# expansions.net
KiCad netlist of a schematic drawn in Altium Designer
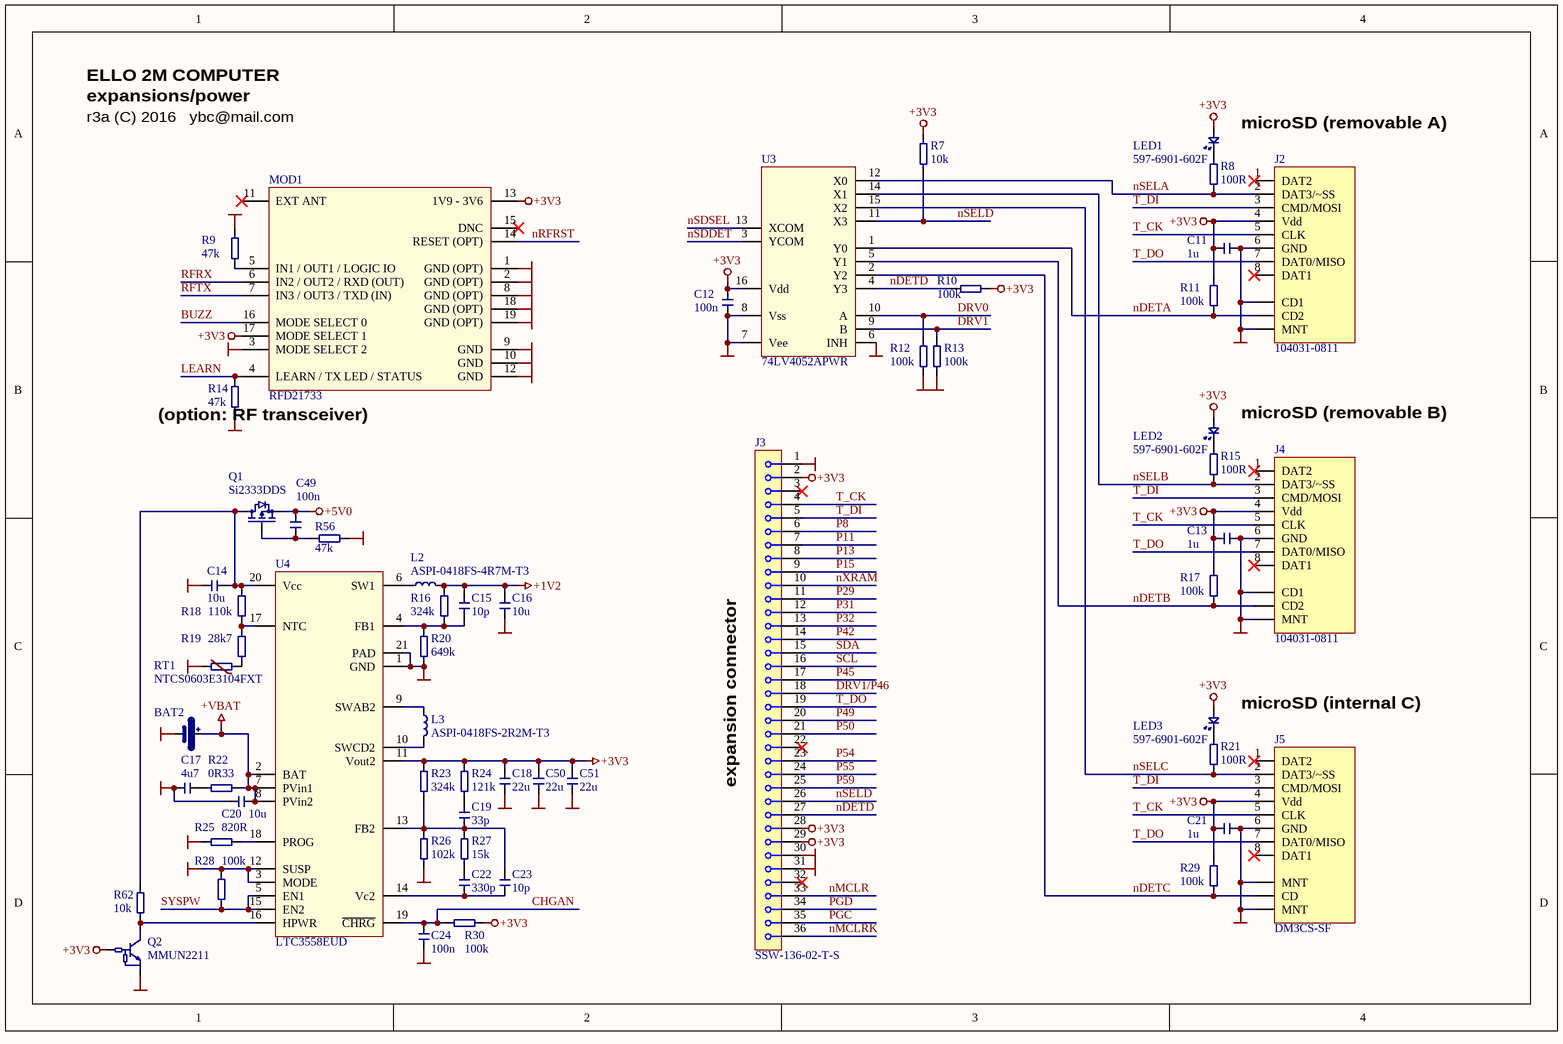
[diagram p0: expansions.SchDoc]

(export (version "E")
  (design (tool "Eeschema 10.0.6"))
  (components
    (comp (ref "BAT2") (value "Battery") (footprint "Bat_Holder1") (libsource (lib "Misc") (part "Battery")))
    (comp (ref "C11")
      (value "1u")
      (footprint "_0603")
      (description "Capacitor")
      (libsource (lib "Discretes") (part "Capacitor"))
    )
    (comp (ref "C12")
      (value "100n")
      (footprint "_0603")
      (description "Capacitor")
      (libsource (lib "Discretes") (part "Capacitor"))
    )
    (comp (ref "C13")
      (value "1u")
      (footprint "_0603")
      (description "Capacitor")
      (libsource (lib "Discretes") (part "Capacitor"))
    )
    (comp (ref "C14")
      (value "10u")
      (footprint "_1206")
      (description "Capacitor")
      (libsource (lib "Discretes") (part "Capacitor"))
    )
    (comp (ref "C15")
      (value "10p")
      (footprint "_0603")
      (description "Capacitor")
      (libsource (lib "Discretes") (part "Capacitor"))
    )
    (comp (ref "C16")
      (value "10u")
      (footprint "_1206")
      (description "Capacitor")
      (libsource (lib "Discretes") (part "Capacitor"))
    )
    (comp (ref "C17")
      (value "4u7")
      (footprint "_1206")
      (description "Capacitor")
      (libsource (lib "Discretes") (part "Capacitor"))
    )
    (comp (ref "C18")
      (value "22u")
      (footprint "_1206")
      (description "Capacitor")
      (libsource (lib "Discretes") (part "Capacitor"))
    )
    (comp (ref "C19")
      (value "33p")
      (footprint "_0603")
      (description "Capacitor")
      (libsource (lib "Discretes") (part "Capacitor"))
    )
    (comp (ref "C20")
      (value "10u")
      (footprint "_1206")
      (description "Capacitor")
      (libsource (lib "Discretes") (part "Capacitor"))
    )
    (comp (ref "C21")
      (value "1u")
      (footprint "_0603")
      (description "Capacitor")
      (libsource (lib "Discretes") (part "Capacitor"))
    )
    (comp (ref "C22")
      (value "330p")
      (footprint "_0603")
      (description "Capacitor")
      (libsource (lib "Discretes") (part "Capacitor"))
    )
    (comp (ref "C23")
      (value "10p")
      (footprint "_0603")
      (description "Capacitor")
      (libsource (lib "Discretes") (part "Capacitor"))
    )
    (comp (ref "C24")
      (value "100n")
      (footprint "_0603")
      (description "Capacitor")
      (libsource (lib "Discretes") (part "Capacitor"))
    )
    (comp (ref "C49")
      (value "100n")
      (footprint "_0603")
      (description "Capacitor")
      (libsource (lib "Discretes") (part "Capacitor"))
    )
    (comp (ref "C50")
      (value "22u")
      (footprint "_1206")
      (description "Capacitor")
      (libsource (lib "Discretes") (part "Capacitor"))
    )
    (comp (ref "C51")
      (value "22u")
      (footprint "_1206")
      (description "Capacitor")
      (libsource (lib "Discretes") (part "Capacitor"))
    )
    (comp (ref "J2")
      (value "104031-0811")
      (footprint "MOLEX_104031")
      (description "microSD card connector")
      (libsource (lib "Connectors") (part "microSD (w/ card detect)"))
    )
    (comp (ref "J3")
      (value "SSW-136-02-T-S")
      (footprint "SSW-136-02-T-S")
      (description "Single row, 36-way connector")
      (libsource (lib "Connectors") (part "Connector 1x36"))
    )
    (comp (ref "J4")
      (value "104031-0811")
      (footprint "MOLEX_104031")
      (description "microSD card connector")
      (libsource (lib "Connectors") (part "microSD (w/ card detect)"))
    )
    (comp (ref "J5")
      (value "DM3CS-SF")
      (footprint "DM3CS-SF")
      (description "microSD card connector")
      (libsource (lib "") (part "microSD (w/ card detect)_1"))
    )
    (comp (ref "L2")
      (value "ASPI-0418FS-4R7M-T3")
      (footprint "IND_4x4")
      (description "Inductor")
      (libsource (lib "") (part "Inductor_1"))
    )
    (comp (ref "L3")
      (value "ASPI-0418FS-2R2M-T3")
      (footprint "IND_4x4")
      (description "Inductor")
      (libsource (lib "Discretes") (part "Inductor"))
    )
    (comp (ref "LED1")
      (value "597-6901-602F")
      (footprint "LED1206 BOTTOM ENTRY")
      (description "Light Emitting Diode")
      (libsource (lib "Discretes") (part "LED"))
    )
    (comp (ref "LED2")
      (value "597-6901-602F")
      (footprint "LED1206 BOTTOM ENTRY")
      (description "Light Emitting Diode")
      (libsource (lib "Discretes") (part "LED"))
    )
    (comp (ref "LED3")
      (value "597-6901-602F")
      (footprint "LED1206 BOTTOM ENTRY")
      (description "Light Emitting Diode")
      (libsource (lib "Discretes") (part "LED"))
    )
    (comp (ref "MOD1")
      (value "RFD21733")
      (footprint "RFDP8")
      (description "Complete 2.4GHz RF transceiver module with built-in RFDP8 application protocol")
      (fields (field (name "MANUFACTURER") "RF Digital"))
      (libsource (lib "Modules") (part "RFDP8"))
    )
    (comp (ref "Q1")
      (value "Si2333DDS")
      (footprint "SOT23-3")
      (description "P-channel FET transistor")
      (libsource (lib "Discretes") (part "P-FET"))
    )
    (comp (ref "Q2")
      (value "MMUN2211")
      (footprint "SOT23-3")
      (description "NPN biased bipolar transistor")
      (libsource (lib "Discretes") (part "NPN BIASED"))
    )
    (comp (ref "R7")
      (value "10k")
      (footprint "_0603")
      (description "Resistor")
      (libsource (lib "") (part "Resistor_1"))
    )
    (comp (ref "R8")
      (value "100R")
      (footprint "_0603")
      (description "Resistor")
      (libsource (lib "") (part "Resistor_2"))
    )
    (comp (ref "R9")
      (value "47k")
      (footprint "_0603")
      (description "Resistor")
      (libsource (lib "") (part "Resistor_1"))
    )
    (comp (ref "R10")
      (value "100k")
      (footprint "_0603")
      (description "Resistor")
      (libsource (lib "") (part "Resistor_3"))
    )
    (comp (ref "R11")
      (value "100k")
      (footprint "_0603")
      (description "Resistor")
      (libsource (lib "") (part "Resistor_2"))
    )
    (comp (ref "R12")
      (value "100k")
      (footprint "_0603")
      (description "Resistor")
      (libsource (lib "") (part "Resistor_1"))
    )
    (comp (ref "R13")
      (value "100k")
      (footprint "_0603")
      (description "Resistor")
      (libsource (lib "") (part "Resistor_1"))
    )
    (comp (ref "R14")
      (value "47k")
      (footprint "_0603")
      (description "Resistor")
      (libsource (lib "") (part "Resistor_1"))
    )
    (comp (ref "R15")
      (value "100R")
      (footprint "_0603")
      (description "Resistor")
      (libsource (lib "") (part "Resistor_2"))
    )
    (comp (ref "R16")
      (value "324k")
      (footprint "_0603")
      (description "Resistor")
      (libsource (lib "Discretes") (part "Resistor"))
    )
    (comp (ref "R17")
      (value "100k")
      (footprint "_0603")
      (description "Resistor")
      (libsource (lib "") (part "Resistor_2"))
    )
    (comp (ref "R18")
      (value "110k")
      (footprint "_0603")
      (description "Resistor")
      (libsource (lib "Discretes") (part "Resistor"))
    )
    (comp (ref "R19")
      (value "28k7")
      (footprint "_0603")
      (description "Resistor")
      (libsource (lib "Discretes") (part "Resistor"))
    )
    (comp (ref "R20")
      (value "649k")
      (footprint "_0603")
      (description "Resistor")
      (libsource (lib "Discretes") (part "Resistor"))
    )
    (comp (ref "R21")
      (value "100R")
      (footprint "_0603")
      (description "Resistor")
      (libsource (lib "") (part "Resistor_2"))
    )
    (comp (ref "R22")
      (value "0R33")
      (footprint "_1206")
      (description "Resistor")
      (libsource (lib "") (part "Resistor_1"))
    )
    (comp (ref "R23")
      (value "324k")
      (footprint "_0603")
      (description "Resistor")
      (libsource (lib "Discretes") (part "Resistor"))
    )
    (comp (ref "R24")
      (value "121k")
      (footprint "_0603")
      (description "Resistor")
      (libsource (lib "Discretes") (part "Resistor"))
    )
    (comp (ref "R25")
      (value "820R")
      (footprint "_0603")
      (description "Resistor")
      (libsource (lib "") (part "Resistor_1"))
    )
    (comp (ref "R26")
      (value "102k")
      (footprint "_0603")
      (description "Resistor")
      (libsource (lib "Discretes") (part "Resistor"))
    )
    (comp (ref "R27")
      (value "15k")
      (footprint "_0603")
      (description "Resistor")
      (libsource (lib "Discretes") (part "Resistor"))
    )
    (comp (ref "R28")
      (value "100k")
      (footprint "_0603")
      (description "Resistor")
      (libsource (lib "Discretes") (part "Resistor"))
    )
    (comp (ref "R29")
      (value "100k")
      (footprint "_0603")
      (description "Resistor")
      (libsource (lib "") (part "Resistor_2"))
    )
    (comp (ref "R30")
      (value "100k")
      (footprint "_0603")
      (description "Resistor")
      (libsource (lib "") (part "Resistor_1"))
    )
    (comp (ref "R56")
      (value "47k")
      (footprint "_0603")
      (description "Resistor")
      (libsource (lib "") (part "Resistor_1"))
    )
    (comp (ref "R62")
      (value "10k")
      (footprint "_0603")
      (description "Resistor")
      (libsource (lib "Discretes") (part "Resistor"))
    )
    (comp (ref "RT1")
      (value "NTCS0603E3104FXT")
      (footprint "_0603")
      (description "Thermistor")
      (libsource (lib "Discretes") (part "Thermistor"))
    )
    (comp (ref "U3")
      (value "74LV4052APWR")
      (footprint "SOP65P640X120-16N")
      (description "Quad CMOS Analog Multiplexers/Demultiplexers with Logic Level Conversion")
      (libsource (lib "IC Drivers and Switches") (part "4052"))
    )
    (comp (ref "U4")
      (value "LTC3558EUD")
      (footprint "QFN40P300X300X70_HS-21N")
      (description "Linear USB Battery Charger with Buck and Buck-Boost Regulators")
      (fields (field (name "MANUFACTURER") "Linear"))
      (libsource (lib "IC Power Supply") (part "LTC3558"))
    )
  )
  (nets
    (net (code "1") (name "+1V2") (class "Default")
      (node (ref "C15") (pin "2") (pintype "passive"))
      (node (ref "C16") (pin "2") (pintype "passive"))
      (node (ref "L2") (pin "1") (pintype "passive"))
      (node (ref "R16") (pin "1") (pintype "passive"))
    )
    (net (code "2") (name "+3V3") (class "Default")
      (node (ref "C11") (pin "1") (pintype "passive"))
      (node (ref "C12") (pin "2") (pintype "passive"))
      (node (ref "C13") (pin "1") (pintype "passive"))
      (node (ref "C18") (pin "2") (pintype "passive"))
      (node (ref "C21") (pin "1") (pintype "passive"))
      (node (ref "C50") (pin "2") (pintype "passive"))
      (node (ref "C51") (pin "2") (pintype "passive"))
      (node (ref "J2") (pin "4") (pinfunction "Vdd_4") (pintype "passive"))
      (node (ref "J3") (pin "2") (pinfunction "2_2") (pintype "passive"))
      (node (ref "J3") (pin "28") (pinfunction "28_28") (pintype "passive"))
      (node (ref "J3") (pin "29") (pinfunction "29_29") (pintype "passive"))
      (node (ref "J4") (pin "4") (pinfunction "Vdd_4") (pintype "passive"))
      (node (ref "J5") (pin "4") (pinfunction "Vdd_4") (pintype "passive"))
      (node (ref "LED1") (pin "2") (pintype "passive"))
      (node (ref "LED2") (pin "2") (pintype "passive"))
      (node (ref "LED3") (pin "2") (pintype "passive"))
      (node (ref "MOD1") (pin "13") (pinfunction "1V9_-_3V6_13") (pintype "power_in"))
      (node (ref "MOD1") (pin "17") (pinfunction "MODE_SELECT_1_17") (pintype "passive"))
      (node (ref "Q2") (pin "1") (pinfunction "B_1") (pintype "passive"))
      (node (ref "R10") (pin "2") (pintype "passive"))
      (node (ref "R11") (pin "1") (pintype "passive"))
      (node (ref "R17") (pin "1") (pintype "passive"))
      (node (ref "R23") (pin "1") (pintype "passive"))
      (node (ref "R24") (pin "1") (pintype "passive"))
      (node (ref "R29") (pin "1") (pintype "passive"))
      (node (ref "R30") (pin "2") (pintype "passive"))
      (node (ref "R7") (pin "2") (pintype "passive"))
      (node (ref "U3") (pin "16") (pinfunction "Vdd_16") (pintype "passive"))
      (node (ref "U4") (pin "11") (pinfunction "Vout2_11") (pintype "passive"))
    )
    (net (code "3") (name "+5V0") (class "Default")
      (node (ref "C49") (pin "2") (pintype "passive"))
      (node (ref "Q1") (pin "2") (pinfunction "S_2") (pintype "passive"))
    )
    (net (code "4") (name "+VBAT") (class "Default")
      (node (ref "BAT2") (pin "1") (pintype "passive"))
      (node (ref "C20") (pin "2") (pintype "passive"))
      (node (ref "R22") (pin "2") (pintype "passive"))
      (node (ref "U4") (pin "2") (pinfunction "BAT_2") (pintype "passive"))
      (node (ref "U4") (pin "7") (pinfunction "PVin1_7") (pintype "passive"))
      (node (ref "U4") (pin "8") (pinfunction "PVin2_8") (pintype "passive"))
    )
    (net (code "5") (name "/BUZZ") (class "Default")
      (node (ref "MOD1") (pin "16") (pinfunction "MODE_SELECT_0_16") (pintype "passive"))
    )
    (net (code "6") (name "/CHGAN") (class "Default")
      (node (ref "C24") (pin "1") (pintype "passive"))
      (node (ref "R30") (pin "1") (pintype "passive"))
      (node (ref "U4") (pin "19") (pinfunction "~{CHRG}_19") (pintype "passive"))
    )
    (net (code "7") (name "/DRV0") (class "Default")
      (node (ref "R12") (pin "2") (pintype "passive"))
      (node (ref "U3") (pin "10") (pinfunction "A_10") (pintype "passive"))
    )
    (net (code "8") (name "/DRV1") (class "Default")
      (node (ref "R13") (pin "2") (pintype "passive"))
      (node (ref "U3") (pin "9") (pinfunction "B_9") (pintype "passive"))
    )
    (net (code "9") (name "/DRV1{slash}P46") (class "Default")
      (node (ref "J3") (pin "18") (pinfunction "18_18") (pintype "passive"))
    )
    (net (code "10") (name "/LEARN") (class "Default")
      (node (ref "MOD1") (pin "4") (pinfunction "LEARN_/_TX_LED_/_STATUS_4") (pintype "passive"))
      (node (ref "R14") (pin "2") (pintype "passive"))
    )
    (net (code "11") (name "/P8") (class "Default")
      (node (ref "J3") (pin "6") (pinfunction "6_6") (pintype "passive"))
    )
    (net (code "12") (name "/P11") (class "Default")
      (node (ref "J3") (pin "7") (pinfunction "7_7") (pintype "passive"))
    )
    (net (code "13") (name "/P13") (class "Default")
      (node (ref "J3") (pin "8") (pinfunction "8_8") (pintype "passive"))
    )
    (net (code "14") (name "/P15") (class "Default")
      (node (ref "J3") (pin "9") (pinfunction "9_9") (pintype "passive"))
    )
    (net (code "15") (name "/P29") (class "Default")
      (node (ref "J3") (pin "11") (pinfunction "11_11") (pintype "passive"))
    )
    (net (code "16") (name "/P31") (class "Default")
      (node (ref "J3") (pin "12") (pinfunction "12_12") (pintype "passive"))
    )
    (net (code "17") (name "/P32") (class "Default")
      (node (ref "J3") (pin "13") (pinfunction "13_13") (pintype "passive"))
    )
    (net (code "18") (name "/P42") (class "Default")
      (node (ref "J3") (pin "14") (pinfunction "14_14") (pintype "passive"))
    )
    (net (code "19") (name "/P45") (class "Default")
      (node (ref "J3") (pin "17") (pinfunction "17_17") (pintype "passive"))
    )
    (net (code "20") (name "/P49") (class "Default")
      (node (ref "J3") (pin "20") (pinfunction "20_20") (pintype "passive"))
    )
    (net (code "21") (name "/P50") (class "Default")
      (node (ref "J3") (pin "21") (pinfunction "21_21") (pintype "passive"))
    )
    (net (code "22") (name "/P54") (class "Default")
      (node (ref "J3") (pin "23") (pinfunction "23_23") (pintype "passive"))
    )
    (net (code "23") (name "/P55") (class "Default")
      (node (ref "J3") (pin "24") (pinfunction "24_24") (pintype "passive"))
    )
    (net (code "24") (name "/P59") (class "Default")
      (node (ref "J3") (pin "25") (pinfunction "25_25") (pintype "passive"))
    )
    (net (code "25") (name "/PGC") (class "Default")
      (node (ref "J3") (pin "35") (pinfunction "35_35") (pintype "passive"))
    )
    (net (code "26") (name "/PGD") (class "Default")
      (node (ref "J3") (pin "34") (pinfunction "34_34") (pintype "passive"))
    )
    (net (code "27") (name "/RFRX") (class "Default")
      (node (ref "MOD1") (pin "6") (pinfunction "IN2_/_OUT2_/_RXD_(OUT)_6") (pintype "passive"))
    )
    (net (code "28") (name "/RFTX") (class "Default")
      (node (ref "MOD1") (pin "7") (pinfunction "IN3_/_OUT3_/_TXD_(IN)_7") (pintype "passive"))
    )
    (net (code "29") (name "/SCL") (class "Default")
      (node (ref "J3") (pin "16") (pinfunction "16_16") (pintype "passive"))
    )
    (net (code "30") (name "/SDA") (class "Default")
      (node (ref "J3") (pin "15") (pinfunction "15_15") (pintype "passive"))
    )
    (net (code "31") (name "/SYSPW") (class "Default")
      (node (ref "R28") (pin "2") (pintype "passive"))
      (node (ref "U4") (pin "15") (pinfunction "EN2_15") (pintype "passive"))
      (node (ref "U4") (pin "5") (pinfunction "EN1_5") (pintype "passive"))
    )
    (net (code "32") (name "/T_CK") (class "Default")
      (node (ref "J2") (pin "5") (pinfunction "CLK_5") (pintype "passive"))
      (node (ref "J3") (pin "4") (pinfunction "4_4") (pintype "passive"))
      (node (ref "J4") (pin "5") (pinfunction "CLK_5") (pintype "passive"))
      (node (ref "J5") (pin "5") (pinfunction "CLK_5") (pintype "passive"))
    )
    (net (code "33") (name "/T_DI") (class "Default")
      (node (ref "J2") (pin "3") (pinfunction "CMD/MOSI_3") (pintype "passive"))
      (node (ref "J3") (pin "5") (pinfunction "5_5") (pintype "passive"))
      (node (ref "J4") (pin "3") (pinfunction "CMD/MOSI_3") (pintype "passive"))
      (node (ref "J5") (pin "3") (pinfunction "CMD/MOSI_3") (pintype "passive"))
    )
    (net (code "34") (name "/T_DO") (class "Default")
      (node (ref "J2") (pin "7") (pinfunction "DAT0/MISO_7") (pintype "passive"))
      (node (ref "J3") (pin "19") (pinfunction "19_19") (pintype "passive"))
      (node (ref "J4") (pin "7") (pinfunction "DAT0/MISO_7") (pintype "passive"))
      (node (ref "J5") (pin "7") (pinfunction "DAT0/MISO_7") (pintype "passive"))
    )
    (net (code "35") (name "/nDETA") (class "Default")
      (node (ref "J2") (pin "CD2") (pinfunction "CD2_CD2") (pintype "passive"))
      (node (ref "R11") (pin "2") (pintype "passive"))
      (node (ref "U3") (pin "1") (pinfunction "Y0_1") (pintype "passive"))
    )
    (net (code "36") (name "/nDETB") (class "Default")
      (node (ref "J4") (pin "CD2") (pinfunction "CD2_CD2") (pintype "passive"))
      (node (ref "R17") (pin "2") (pintype "passive"))
      (node (ref "U3") (pin "5") (pinfunction "Y1_5") (pintype "passive"))
    )
    (net (code "37") (name "/nDETC") (class "Default")
      (node (ref "J5") (pin "CD") (pinfunction "CD_CD") (pintype "passive"))
      (node (ref "R29") (pin "2") (pintype "passive"))
      (node (ref "U3") (pin "2") (pinfunction "Y2_2") (pintype "passive"))
    )
    (net (code "38") (name "/nDETD") (class "Default")
      (node (ref "J3") (pin "27") (pinfunction "27_27") (pintype "passive"))
      (node (ref "R10") (pin "1") (pintype "passive"))
      (node (ref "U3") (pin "4") (pinfunction "Y3_4") (pintype "passive"))
    )
    (net (code "39") (name "/nMCLR") (class "Default")
      (node (ref "J3") (pin "33") (pinfunction "33_33") (pintype "passive"))
    )
    (net (code "40") (name "/nMCLRK") (class "Default")
      (node (ref "J3") (pin "36") (pinfunction "36_36") (pintype "passive"))
    )
    (net (code "41") (name "/nRFRST") (class "Default")
      (node (ref "MOD1") (pin "14") (pinfunction "RESET_(OPT)_14") (pintype "passive"))
    )
    (net (code "42") (name "/nSDDET") (class "Default")
      (node (ref "U3") (pin "3") (pinfunction "YCOM_3") (pintype "passive"))
    )
    (net (code "43") (name "/nSDSEL") (class "Default")
      (node (ref "U3") (pin "13") (pinfunction "XCOM_13") (pintype "passive"))
    )
    (net (code "44") (name "/nSELA") (class "Default")
      (node (ref "J2") (pin "2") (pinfunction "DAT3/~SS_2") (pintype "passive"))
      (node (ref "R8") (pin "2") (pintype "passive"))
      (node (ref "U3") (pin "12") (pinfunction "X0_12") (pintype "passive"))
    )
    (net (code "45") (name "/nSELB") (class "Default")
      (node (ref "J4") (pin "2") (pinfunction "DAT3/~SS_2") (pintype "passive"))
      (node (ref "R15") (pin "2") (pintype "passive"))
      (node (ref "U3") (pin "14") (pinfunction "X1_14") (pintype "passive"))
    )
    (net (code "46") (name "/nSELC") (class "Default")
      (node (ref "J5") (pin "2") (pinfunction "DAT3/~SS_2") (pintype "passive"))
      (node (ref "R21") (pin "2") (pintype "passive"))
      (node (ref "U3") (pin "15") (pinfunction "X2_15") (pintype "passive"))
    )
    (net (code "47") (name "/nSELD") (class "Default")
      (node (ref "J3") (pin "26") (pinfunction "26_26") (pintype "passive"))
      (node (ref "R7") (pin "1") (pintype "passive"))
      (node (ref "U3") (pin "11") (pinfunction "X3_11") (pintype "passive"))
    )
    (net (code "48") (name "/nXRAM") (class "Default")
      (node (ref "J3") (pin "10") (pinfunction "10_10") (pintype "passive"))
    )
    (net (code "49") (name "GND") (class "Default")
      (node (ref "BAT2") (pin "2") (pintype "passive"))
      (node (ref "C11") (pin "2") (pintype "passive"))
      (node (ref "C12") (pin "1") (pintype "passive"))
      (node (ref "C13") (pin "2") (pintype "passive"))
      (node (ref "C14") (pin "2") (pintype "passive"))
      (node (ref "C16") (pin "1") (pintype "passive"))
      (node (ref "C17") (pin "1") (pintype "passive"))
      (node (ref "C18") (pin "1") (pintype "passive"))
      (node (ref "C20") (pin "1") (pintype "passive"))
      (node (ref "C21") (pin "2") (pintype "passive"))
      (node (ref "C24") (pin "2") (pintype "passive"))
      (node (ref "C50") (pin "1") (pintype "passive"))
      (node (ref "C51") (pin "1") (pintype "passive"))
      (node (ref "J2") (pin "6") (pinfunction "GND_6") (pintype "passive"))
      (node (ref "J2") (pin "CD1") (pinfunction "CD1_CD1") (pintype "passive"))
      (node (ref "J2") (pin "MNT") (pinfunction "MNT_MNT") (pintype "passive"))
      (node (ref "J3") (pin "1") (pinfunction "1_1") (pintype "passive"))
      (node (ref "J3") (pin "30") (pinfunction "30_30") (pintype "passive"))
      (node (ref "J3") (pin "31") (pinfunction "31_31") (pintype "passive"))
      (node (ref "J4") (pin "6") (pinfunction "GND_6") (pintype "passive"))
      (node (ref "J4") (pin "CD1") (pinfunction "CD1_CD1") (pintype "passive"))
      (node (ref "J4") (pin "MNT") (pinfunction "MNT_MNT") (pintype "passive"))
      (node (ref "J5") (pin "0") (pinfunction "MNT_0") (pintype "passive"))
      (node (ref "J5") (pin "6") (pinfunction "GND_6") (pintype "passive"))
      (node (ref "MOD1") (pin "1") (pinfunction "GND_(OPT)_1") (pintype "passive"))
      (node (ref "MOD1") (pin "10") (pinfunction "GND_10") (pintype "power_in"))
      (node (ref "MOD1") (pin "12") (pinfunction "GND_12") (pintype "power_in"))
      (node (ref "MOD1") (pin "18") (pinfunction "GND_(OPT)_18") (pintype "passive"))
      (node (ref "MOD1") (pin "19") (pinfunction "GND_(OPT)_19") (pintype "passive"))
      (node (ref "MOD1") (pin "2") (pinfunction "GND_(OPT)_2") (pintype "passive"))
      (node (ref "MOD1") (pin "3") (pinfunction "MODE_SELECT_2_3") (pintype "passive"))
      (node (ref "MOD1") (pin "8") (pinfunction "GND_(OPT)_8") (pintype "passive"))
      (node (ref "MOD1") (pin "9") (pinfunction "GND_9") (pintype "power_in"))
      (node (ref "Q2") (pin "2") (pinfunction "E_2") (pintype "passive"))
      (node (ref "R12") (pin "1") (pintype "passive"))
      (node (ref "R13") (pin "1") (pintype "passive"))
      (node (ref "R14") (pin "1") (pintype "passive"))
      (node (ref "R20") (pin "2") (pintype "passive"))
      (node (ref "R25") (pin "1") (pintype "passive"))
      (node (ref "R26") (pin "2") (pintype "passive"))
      (node (ref "R28") (pin "1") (pintype "passive"))
      (node (ref "R56") (pin "2") (pintype "passive"))
      (node (ref "R9") (pin "2") (pintype "passive"))
      (node (ref "RT1") (pin "2") (pintype "passive"))
      (node (ref "U3") (pin "6") (pinfunction "INH_6") (pintype "passive"))
      (node (ref "U3") (pin "7") (pinfunction "Vee_7") (pintype "passive"))
      (node (ref "U3") (pin "8") (pinfunction "Vss_8") (pintype "passive"))
      (node (ref "U4") (pin "1") (pinfunction "GND_1") (pintype "passive"))
      (node (ref "U4") (pin "12") (pinfunction "SUSP_12") (pintype "passive"))
      (node (ref "U4") (pin "21") (pinfunction "PAD_21") (pintype "passive"))
      (node (ref "U4") (pin "3") (pinfunction "MODE_3") (pintype "passive"))
    )
    (net (code "50") (name "Net-(C17-Pad2)") (class "Default")
      (node (ref "C17") (pin "2") (pintype "passive"))
      (node (ref "R22") (pin "1") (pintype "passive"))
    )
    (net (code "51") (name "Net-(C19-Pad2)") (class "Default")
      (node (ref "C19") (pin "2") (pintype "passive"))
      (node (ref "R24") (pin "2") (pintype "passive"))
    )
    (net (code "52") (name "Net-(C22-Pad2)") (class "Default")
      (node (ref "C22") (pin "2") (pintype "passive"))
      (node (ref "R27") (pin "2") (pintype "passive"))
    )
    (net (code "53") (name "Net-(LED1-Pad1)") (class "Default")
      (node (ref "LED1") (pin "1") (pintype "passive"))
      (node (ref "R8") (pin "1") (pintype "passive"))
    )
    (net (code "54") (name "Net-(LED2-Pad1)") (class "Default")
      (node (ref "LED2") (pin "1") (pintype "passive"))
      (node (ref "R15") (pin "1") (pintype "passive"))
    )
    (net (code "55") (name "Net-(LED3-Pad1)") (class "Default")
      (node (ref "LED3") (pin "1") (pintype "passive"))
      (node (ref "R21") (pin "1") (pintype "passive"))
    )
    (net (code "56") (name "Net-(MOD1-IN1_{slash}_OUT1_{slash}_LOGIC_IO)") (class "Default")
      (node (ref "MOD1") (pin "5") (pinfunction "IN1_/_OUT1_/_LOGIC_IO_5") (pintype "passive"))
      (node (ref "R9") (pin "1") (pintype "passive"))
    )
    (net (code "57") (name "Net-(Q1-D)") (class "Default")
      (node (ref "C14") (pin "1") (pintype "passive"))
      (node (ref "Q1") (pin "3") (pinfunction "D_3") (pintype "passive"))
      (node (ref "R18") (pin "1") (pintype "passive"))
      (node (ref "R62") (pin "1") (pintype "passive"))
      (node (ref "U4") (pin "20") (pinfunction "Vcc_20") (pintype "passive"))
    )
    (net (code "58") (name "Net-(Q1-G)") (class "Default")
      (node (ref "C49") (pin "1") (pintype "passive"))
      (node (ref "Q1") (pin "1") (pinfunction "G_1") (pintype "passive"))
      (node (ref "R56") (pin "1") (pintype "passive"))
    )
    (net (code "59") (name "Net-(Q2-C)") (class "Default")
      (node (ref "Q2") (pin "3") (pinfunction "C_3") (pintype "passive"))
      (node (ref "R62") (pin "2") (pintype "passive"))
      (node (ref "U4") (pin "16") (pinfunction "HPWR_16") (pintype "passive"))
    )
    (net (code "60") (name "Net-(R19-Pad2)") (class "Default")
      (node (ref "R19") (pin "2") (pintype "passive"))
      (node (ref "RT1") (pin "1") (pintype "passive"))
    )
    (net (code "61") (name "Net-(U4-FB1)") (class "Default")
      (node (ref "C15") (pin "1") (pintype "passive"))
      (node (ref "R16") (pin "2") (pintype "passive"))
      (node (ref "R20") (pin "1") (pintype "passive"))
      (node (ref "U4") (pin "4") (pinfunction "FB1_4") (pintype "passive"))
    )
    (net (code "62") (name "Net-(U4-FB2)") (class "Default")
      (node (ref "C19") (pin "1") (pintype "passive"))
      (node (ref "C23") (pin "2") (pintype "passive"))
      (node (ref "R23") (pin "2") (pintype "passive"))
      (node (ref "R26") (pin "1") (pintype "passive"))
      (node (ref "R27") (pin "1") (pintype "passive"))
      (node (ref "U4") (pin "13") (pinfunction "FB2_13") (pintype "passive"))
    )
    (net (code "63") (name "Net-(U4-NTC)") (class "Default")
      (node (ref "R18") (pin "2") (pintype "passive"))
      (node (ref "R19") (pin "1") (pintype "passive"))
      (node (ref "U4") (pin "17") (pinfunction "NTC_17") (pintype "passive"))
    )
    (net (code "64") (name "Net-(U4-PROG)") (class "Default")
      (node (ref "R25") (pin "2") (pintype "passive"))
      (node (ref "U4") (pin "18") (pinfunction "PROG_18") (pintype "passive"))
    )
    (net (code "65") (name "Net-(U4-SW1)") (class "Default")
      (node (ref "L2") (pin "2") (pintype "passive"))
      (node (ref "U4") (pin "6") (pinfunction "SW1_6") (pintype "passive"))
    )
    (net (code "66") (name "Net-(U4-SWAB2)") (class "Default")
      (node (ref "L3") (pin "2") (pintype "passive"))
      (node (ref "U4") (pin "9") (pinfunction "SWAB2_9") (pintype "passive"))
    )
    (net (code "67") (name "Net-(U4-SWCD2)") (class "Default")
      (node (ref "L3") (pin "1") (pintype "passive"))
      (node (ref "U4") (pin "10") (pinfunction "SWCD2_10") (pintype "passive"))
    )
    (net (code "68") (name "Net-(U4-Vc2)") (class "Default")
      (node (ref "C22") (pin "1") (pintype "passive"))
      (node (ref "C23") (pin "1") (pintype "passive"))
      (node (ref "U4") (pin "14") (pinfunction "Vc2_14") (pintype "passive"))
    )
    (net (code "69") (name "unconnected-(J2-DAT1-Pad8)") (class "Default")
      (node (ref "J2") (pin "8") (pinfunction "DAT1_8") (pintype "passive+no_connect"))
    )
    (net (code "70") (name "unconnected-(J2-DAT2-Pad1)") (class "Default")
      (node (ref "J2") (pin "1") (pinfunction "DAT2_1") (pintype "passive+no_connect"))
    )
    (net (code "71") (name "unconnected-(J3-Pad3)") (class "Default")
      (node (ref "J3") (pin "3") (pinfunction "3_3") (pintype "passive+no_connect"))
    )
    (net (code "72") (name "unconnected-(J3-Pad22)") (class "Default")
      (node (ref "J3") (pin "22") (pinfunction "22_22") (pintype "passive+no_connect"))
    )
    (net (code "73") (name "unconnected-(J3-Pad32)") (class "Default")
      (node (ref "J3") (pin "32") (pinfunction "32_32") (pintype "passive+no_connect"))
    )
    (net (code "74") (name "unconnected-(J4-DAT1-Pad8)") (class "Default")
      (node (ref "J4") (pin "8") (pinfunction "DAT1_8") (pintype "passive+no_connect"))
    )
    (net (code "75") (name "unconnected-(J4-DAT2-Pad1)") (class "Default")
      (node (ref "J4") (pin "1") (pinfunction "DAT2_1") (pintype "passive+no_connect"))
    )
    (net (code "76") (name "unconnected-(J5-DAT1-Pad8)") (class "Default")
      (node (ref "J5") (pin "8") (pinfunction "DAT1_8") (pintype "passive+no_connect"))
    )
    (net (code "77") (name "unconnected-(J5-DAT2-Pad1)") (class "Default")
      (node (ref "J5") (pin "1") (pinfunction "DAT2_1") (pintype "passive+no_connect"))
    )
    (net (code "78") (name "unconnected-(MOD1-DNC-Pad15)") (class "Default")
      (node (ref "MOD1") (pin "15") (pinfunction "DNC_15") (pintype "passive+no_connect"))
    )
    (net (code "79") (name "unconnected-(MOD1-EXT_ANT-Pad11)") (class "Default")
      (node (ref "MOD1") (pin "11") (pinfunction "EXT_ANT_11") (pintype "passive+no_connect"))
    )
  )
)
